# Stm32.net
KiCad netlist of a schematic drawn in Altium Designer
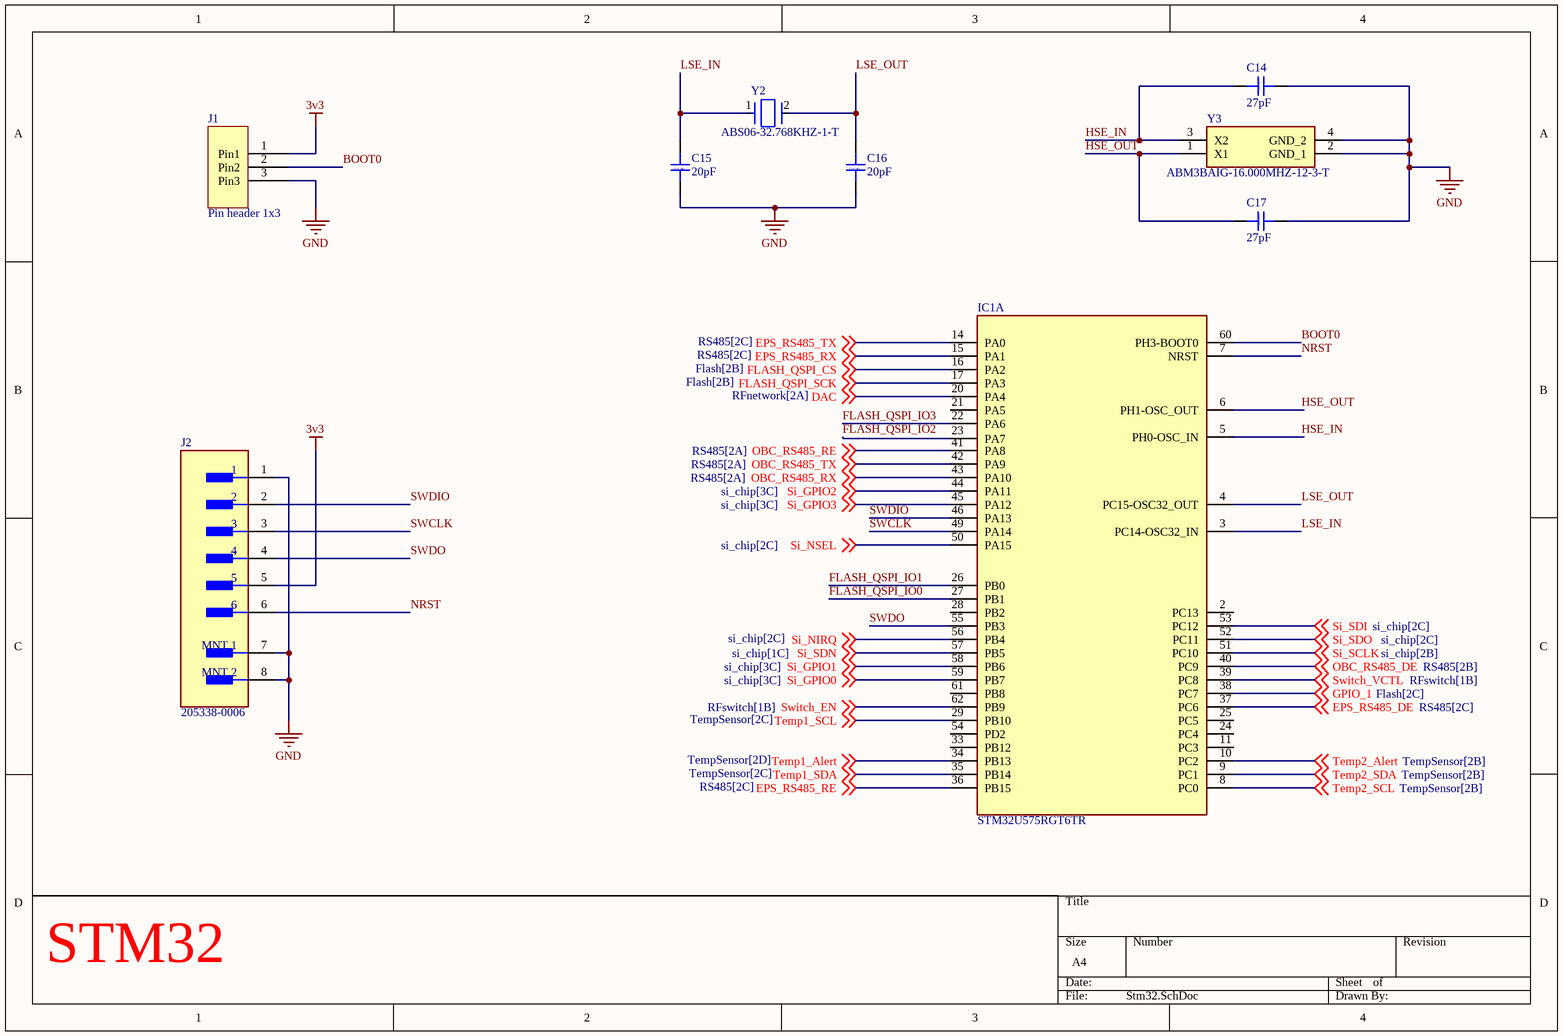
[diagram p0: Stm32.SchDoc]

(export (version "E")
  (design (tool "Eeschema 10.0.6"))
  (components
    (comp (ref "C14")
      (value "27pF")
      (footprint "CAP_0603")
      (description "Capacitor SMD 0603 RATED")
      (libsource (lib "STeRG-Passives-Standard") (part "Capacitor-SMD-0603"))
    )
    (comp (ref "C15")
      (value "20pF")
      (footprint "CAP_0603")
      (description "Capacitor SMD 0603 RATED")
      (libsource (lib "STeRG-Passives-Standard") (part "Capacitor-SMD-0603"))
    )
    (comp (ref "C16")
      (value "20pF")
      (footprint "CAP_0603")
      (description "Capacitor SMD 0603 RATED")
      (libsource (lib "STeRG-Passives-Standard") (part "Capacitor-SMD-0603"))
    )
    (comp (ref "C17")
      (value "27pF")
      (footprint "CAP_0603")
      (description "Capacitor SMD 0603 RATED")
      (libsource (lib "STeRG-Passives-Standard") (part "Capacitor-SMD-0603"))
    )
    (comp (ref "IC1")
      (value "STM32U575RGT6TR")
      (footprint "QFP50P1200X1200X160-64N")
      (description "Integrated Circuit")
      (fields (field (name "MOUSER PART NUMBER") "511-STM32U575RGT6TR"))
      (libsource (lib "STeRG-ICs-Standard") (part "STM32U575RGT6TR"))
    )
    (comp (ref "J1")
      (value "Pin header 1x3")
      (footprint "HEADER 3")
      (libsource (lib "SamacSys") (part "Pin header 1x3"))
    )
    (comp (ref "J2")
      (value "205338-0006")
      (footprint "FP-2053380006-MFG")
      (libsource (lib "Altium Content Vault") (part "ed24c53d9ba001d1a2a686240a95171"))
    )
    (comp (ref "Y2")
      (value "ABS06-32.768KHZ-1-T")
      (footprint "FP-ABS06-MFG")
      (description "CRYSTAL 32.7680KHZ 12.5PF SMD")
      (fields (field (name "TOLERANCE") "10ppm"))
      (libsource (lib "Altium Content Vault") (part "c23a69dc6c9e2f18f2079038eb95dd1"))
    )
    (comp (ref "Y3")
      (value "ABM3BAIG-16.000MHZ-12-3-T")
      (footprint "SamacSys:ABM3BAIG")
      (description "Crystal or Oscillator")
      (libsource (lib "SamacSys") (part "ABM3BAIG-16.000MHZ-12-3-T"))
    )
  )
  (nets
    (net (code "1") (name "/BOOT0") (class "Default")
      (node (ref "IC1") (pin "60") (pinfunction "PH3-BOOT0_60") (pintype "passive"))
      (node (ref "J1") (pin "2") (pinfunction "Pin2_2") (pintype "passive"))
    )
    (net (code "2") (name "/FLASH_QSPI_IO0") (class "Default")
      (node (ref "IC1") (pin "27") (pinfunction "PB1_27") (pintype "passive"))
    )
    (net (code "3") (name "/FLASH_QSPI_IO1") (class "Default")
      (node (ref "IC1") (pin "26") (pinfunction "PB0_26") (pintype "passive"))
    )
    (net (code "4") (name "/FLASH_QSPI_IO2") (class "Default")
      (node (ref "IC1") (pin "23") (pinfunction "PA7_23") (pintype "passive"))
    )
    (net (code "5") (name "/FLASH_QSPI_IO3") (class "Default")
      (node (ref "IC1") (pin "22") (pinfunction "PA6_22") (pintype "passive"))
    )
    (net (code "6") (name "/HSE_IN") (class "Default")
      (node (ref "C14") (pin "1") (pinfunction "1_1") (pintype "passive"))
      (node (ref "IC1") (pin "5") (pinfunction "PH0-OSC_IN_5") (pintype "passive"))
      (node (ref "Y3") (pin "3") (pinfunction "X2_3") (pintype "passive"))
    )
    (net (code "7") (name "/HSE_OUT") (class "Default")
      (node (ref "C17") (pin "1") (pinfunction "1_1") (pintype "passive"))
      (node (ref "IC1") (pin "6") (pinfunction "PH1-OSC_OUT_6") (pintype "passive"))
      (node (ref "Y3") (pin "1") (pinfunction "X1_1") (pintype "passive"))
    )
    (net (code "8") (name "/LSE_IN") (class "Default")
      (node (ref "C15") (pin "2") (pinfunction "2_2") (pintype "passive"))
      (node (ref "IC1") (pin "3") (pinfunction "PC14-OSC32_IN_3") (pintype "passive"))
      (node (ref "Y2") (pin "1") (pinfunction "1_1") (pintype "passive"))
    )
    (net (code "9") (name "/LSE_OUT") (class "Default")
      (node (ref "C16") (pin "2") (pinfunction "2_2") (pintype "passive"))
      (node (ref "IC1") (pin "4") (pinfunction "PC15-OSC32_OUT_4") (pintype "passive"))
      (node (ref "Y2") (pin "2") (pinfunction "2_2") (pintype "passive"))
    )
    (net (code "10") (name "/NRST") (class "Default")
      (node (ref "IC1") (pin "7") (pinfunction "NRST_7") (pintype "passive"))
      (node (ref "J2") (pin "6") (pinfunction "6_6") (pintype "passive"))
    )
    (net (code "11") (name "/SWCLK") (class "Default")
      (node (ref "IC1") (pin "49") (pinfunction "PA14_49") (pintype "passive"))
      (node (ref "J2") (pin "3") (pinfunction "3_3") (pintype "passive"))
    )
    (net (code "12") (name "/SWDIO") (class "Default")
      (node (ref "IC1") (pin "46") (pinfunction "PA13_46") (pintype "passive"))
      (node (ref "J2") (pin "2") (pinfunction "2_2") (pintype "passive"))
    )
    (net (code "13") (name "/SWDO") (class "Default")
      (node (ref "IC1") (pin "55") (pinfunction "PB3_55") (pintype "passive"))
      (node (ref "J2") (pin "4") (pinfunction "4_4") (pintype "passive"))
    )
    (net (code "14") (name "3v3") (class "Default")
      (node (ref "J1") (pin "1") (pinfunction "Pin1_1") (pintype "passive"))
      (node (ref "J2") (pin "5") (pinfunction "5_5") (pintype "passive"))
    )
    (net (code "15") (name "DAC") (class "Default")
      (node (ref "IC1") (pin "20") (pinfunction "PA4_20") (pintype "passive"))
    )
    (net (code "16") (name "EPS_RS485_DE") (class "Default")
      (node (ref "IC1") (pin "37") (pinfunction "PC6_37") (pintype "passive"))
    )
    (net (code "17") (name "EPS_RS485_RE") (class "Default")
      (node (ref "IC1") (pin "36") (pinfunction "PB15_36") (pintype "passive"))
    )
    (net (code "18") (name "EPS_RS485_RX") (class "Default")
      (node (ref "IC1") (pin "15") (pinfunction "PA1_15") (pintype "passive"))
    )
    (net (code "19") (name "EPS_RS485_TX") (class "Default")
      (node (ref "IC1") (pin "14") (pinfunction "PA0_14") (pintype "passive"))
    )
    (net (code "20") (name "FLASH_QSPI_CS") (class "Default")
      (node (ref "IC1") (pin "16") (pinfunction "PA2_16") (pintype "passive"))
    )
    (net (code "21") (name "FLASH_QSPI_SCK") (class "Default")
      (node (ref "IC1") (pin "17") (pinfunction "PA3_17") (pintype "passive"))
    )
    (net (code "22") (name "GND") (class "Default")
      (node (ref "C14") (pin "2") (pinfunction "2_2") (pintype "passive"))
      (node (ref "C15") (pin "1") (pinfunction "1_1") (pintype "passive"))
      (node (ref "C16") (pin "1") (pinfunction "1_1") (pintype "passive"))
      (node (ref "C17") (pin "2") (pinfunction "2_2") (pintype "passive"))
      (node (ref "J1") (pin "3") (pinfunction "Pin3_3") (pintype "passive"))
      (node (ref "J2") (pin "1") (pinfunction "1_1") (pintype "passive"))
      (node (ref "J2") (pin "7") (pinfunction "MNT_1_7") (pintype "passive"))
      (node (ref "J2") (pin "8") (pinfunction "MNT_2_8") (pintype "passive"))
      (node (ref "Y3") (pin "2") (pinfunction "GND_1_2") (pintype "passive"))
      (node (ref "Y3") (pin "4") (pinfunction "GND_2_4") (pintype "passive"))
    )
    (net (code "23") (name "GPIO_1") (class "Default")
      (node (ref "IC1") (pin "38") (pinfunction "PC7_38") (pintype "passive"))
    )
    (net (code "24") (name "OBC_RS485_DE") (class "Default")
      (node (ref "IC1") (pin "40") (pinfunction "PC9_40") (pintype "passive"))
    )
    (net (code "25") (name "OBC_RS485_RE") (class "Default")
      (node (ref "IC1") (pin "41") (pinfunction "PA8_41") (pintype "passive"))
    )
    (net (code "26") (name "OBC_RS485_RX") (class "Default")
      (node (ref "IC1") (pin "43") (pinfunction "PA10_43") (pintype "passive"))
    )
    (net (code "27") (name "OBC_RS485_TX") (class "Default")
      (node (ref "IC1") (pin "42") (pinfunction "PA9_42") (pintype "passive"))
    )
    (net (code "28") (name "Si_GPIO0") (class "Default")
      (node (ref "IC1") (pin "59") (pinfunction "PB7_59") (pintype "passive"))
    )
    (net (code "29") (name "Si_GPIO1") (class "Default")
      (node (ref "IC1") (pin "58") (pinfunction "PB6_58") (pintype "passive"))
    )
    (net (code "30") (name "Si_GPIO2") (class "Default")
      (node (ref "IC1") (pin "44") (pinfunction "PA11_44") (pintype "passive"))
    )
    (net (code "31") (name "Si_GPIO3") (class "Default")
      (node (ref "IC1") (pin "45") (pinfunction "PA12_45") (pintype "passive"))
    )
    (net (code "32") (name "Si_NIRQ") (class "Default")
      (node (ref "IC1") (pin "56") (pinfunction "PB4_56") (pintype "passive"))
    )
    (net (code "33") (name "Si_NSEL") (class "Default")
      (node (ref "IC1") (pin "50") (pinfunction "PA15_50") (pintype "passive"))
    )
    (net (code "34") (name "Si_SCLK") (class "Default")
      (node (ref "IC1") (pin "51") (pinfunction "PC10_51") (pintype "passive"))
    )
    (net (code "35") (name "Si_SDI") (class "Default")
      (node (ref "IC1") (pin "53") (pinfunction "PC12_53") (pintype "passive"))
    )
    (net (code "36") (name "Si_SDN") (class "Default")
      (node (ref "IC1") (pin "57") (pinfunction "PB5_57") (pintype "passive"))
    )
    (net (code "37") (name "Si_SDO") (class "Default")
      (node (ref "IC1") (pin "52") (pinfunction "PC11_52") (pintype "passive"))
    )
    (net (code "38") (name "Switch_EN") (class "Default")
      (node (ref "IC1") (pin "62") (pinfunction "PB9_62") (pintype "passive"))
    )
    (net (code "39") (name "Switch_VCTL") (class "Default")
      (node (ref "IC1") (pin "39") (pinfunction "PC8_39") (pintype "passive"))
    )
    (net (code "40") (name "Temp1_Alert") (class "Default")
      (node (ref "IC1") (pin "34") (pinfunction "PB13_34") (pintype "passive"))
    )
    (net (code "41") (name "Temp1_SCL") (class "Default")
      (node (ref "IC1") (pin "29") (pinfunction "PB10_29") (pintype "passive"))
    )
    (net (code "42") (name "Temp1_SDA") (class "Default")
      (node (ref "IC1") (pin "35") (pinfunction "PB14_35") (pintype "passive"))
    )
    (net (code "43") (name "Temp2_Alert") (class "Default")
      (node (ref "IC1") (pin "10") (pinfunction "PC2_10") (pintype "passive"))
    )
    (net (code "44") (name "Temp2_SCL") (class "Default")
      (node (ref "IC1") (pin "8") (pinfunction "PC0_8") (pintype "passive"))
    )
    (net (code "45") (name "Temp2_SDA") (class "Default")
      (node (ref "IC1") (pin "9") (pinfunction "PC1_9") (pintype "passive"))
    )
    (net (code "46") (name "unconnected-(IC1A-PA5-Pad21)") (class "Default")
      (node (ref "IC1") (pin "21") (pinfunction "PA5_21") (pintype "passive"))
    )
    (net (code "47") (name "unconnected-(IC1A-PB2-Pad28)") (class "Default")
      (node (ref "IC1") (pin "28") (pinfunction "PB2_28") (pintype "passive"))
    )
    (net (code "48") (name "unconnected-(IC1A-PB8-Pad61)") (class "Default")
      (node (ref "IC1") (pin "61") (pinfunction "PB8_61") (pintype "passive"))
    )
    (net (code "49") (name "unconnected-(IC1A-PB12-Pad33)") (class "Default")
      (node (ref "IC1") (pin "33") (pinfunction "PB12_33") (pintype "passive"))
    )
    (net (code "50") (name "unconnected-(IC1A-PC3-Pad11)") (class "Default")
      (node (ref "IC1") (pin "11") (pinfunction "PC3_11") (pintype "passive"))
    )
    (net (code "51") (name "unconnected-(IC1A-PC4-Pad24)") (class "Default")
      (node (ref "IC1") (pin "24") (pinfunction "PC4_24") (pintype "passive"))
    )
    (net (code "52") (name "unconnected-(IC1A-PC5-Pad25)") (class "Default")
      (node (ref "IC1") (pin "25") (pinfunction "PC5_25") (pintype "passive"))
    )
    (net (code "53") (name "unconnected-(IC1A-PC13-Pad2)") (class "Default")
      (node (ref "IC1") (pin "2") (pinfunction "PC13_2") (pintype "passive"))
    )
    (net (code "54") (name "unconnected-(IC1A-PD2-Pad54)") (class "Default")
      (node (ref "IC1") (pin "54") (pinfunction "PD2_54") (pintype "passive"))
    )
  )
)
